# Thermal_imager_Up.net
KiCad netlist of a schematic drawn in Altium Designer
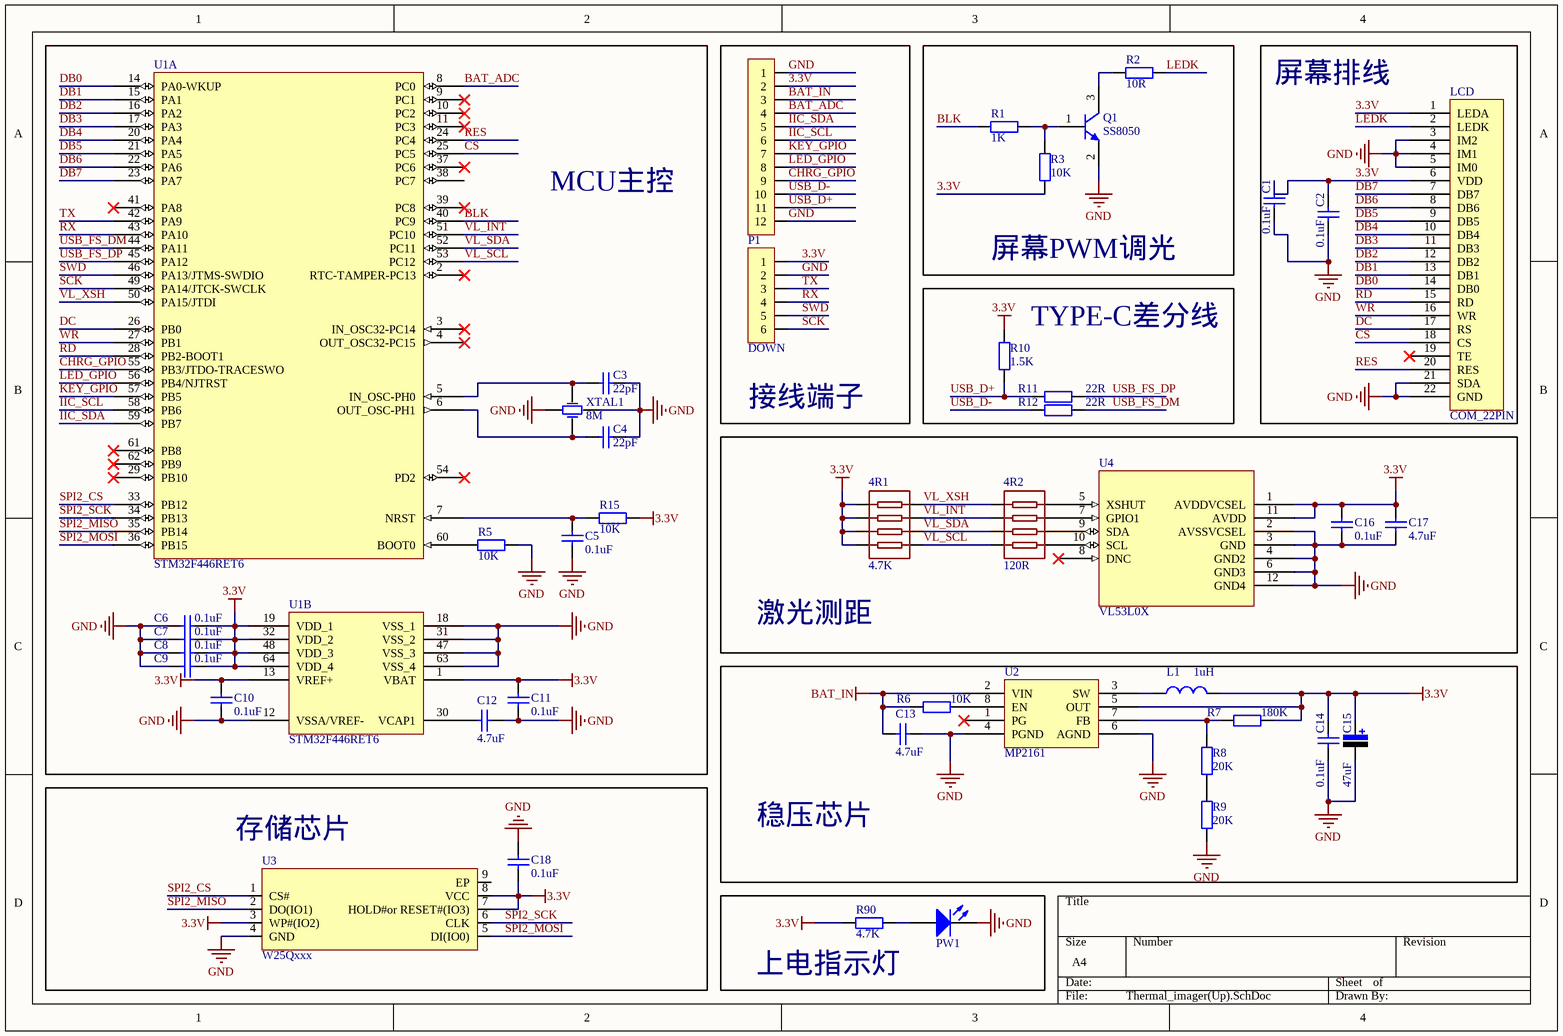
[diagram p0: Thermal_imager(Up).SchDoc]

(export (version "E")
  (design (tool "Eeschema 10.0.6"))
  (components
    (comp (ref "4R1") (value "4.7K") (footprint "R_4R") (libsource (lib "Zfy_Library") (part "4R")))
    (comp (ref "4R2") (value "120R") (footprint "R_4R") (libsource (lib "Zfy_Library") (part "4R")))
    (comp (ref "C1")
      (value "0.1uF")
      (footprint "LC-0603_C")
      (description "无极性电容")
      (fields (field (name "PUBLISHER") "Altium Limited"))
      (libsource (lib "Fszhang") (part "Cap"))
    )
    (comp (ref "C2")
      (value "0.1uF")
      (footprint "LC-0603_C")
      (description "无极性电容")
      (fields (field (name "PUBLISHER") "Altium Limited"))
      (libsource (lib "Fszhang") (part "Cap"))
    )
    (comp (ref "C3")
      (value "22pF")
      (footprint "LC-0603_C")
      (description "无极性电容")
      (fields (field (name "Comment") "Cap") (field (name "PUBLISHER") "Altium Limited"))
      (libsource (lib "Fszhang") (part "Cap"))
    )
    (comp (ref "C4")
      (value "22pF")
      (footprint "LC-0603_C")
      (description "无极性电容")
      (fields (field (name "Comment") "Cap") (field (name "PUBLISHER") "Altium Limited"))
      (libsource (lib "Fszhang") (part "Cap"))
    )
    (comp (ref "C5")
      (value "0.1uF")
      (footprint "LC-0603_C")
      (description "无极性电容")
      (fields (field (name "PUBLISHER") "Altium Limited"))
      (libsource (lib "Fszhang") (part "Cap"))
    )
    (comp (ref "C6")
      (value "0.1uF")
      (footprint "LC-0603_C")
      (description "无极性电容")
      (fields (field (name "PUBLISHER") "Altium Limited"))
      (libsource (lib "Fszhang") (part "Cap"))
    )
    (comp (ref "C7")
      (value "0.1uF")
      (footprint "LC-0603_C")
      (description "无极性电容")
      (fields (field (name "PUBLISHER") "Altium Limited"))
      (libsource (lib "Fszhang") (part "Cap"))
    )
    (comp (ref "C8")
      (value "0.1uF")
      (footprint "LC-0603_C")
      (description "无极性电容")
      (fields (field (name "PUBLISHER") "Altium Limited"))
      (libsource (lib "Fszhang") (part "Cap"))
    )
    (comp (ref "C9")
      (value "0.1uF")
      (footprint "LC-0603_C")
      (description "无极性电容")
      (fields (field (name "PUBLISHER") "Altium Limited"))
      (libsource (lib "Fszhang") (part "Cap"))
    )
    (comp (ref "C10")
      (value "0.1uF")
      (footprint "LC-0603_C")
      (description "无极性电容")
      (fields (field (name "PUBLISHER") "Altium Limited"))
      (libsource (lib "Fszhang") (part "Cap"))
    )
    (comp (ref "C11")
      (value "0.1uF")
      (footprint "LC-0603_C")
      (description "无极性电容")
      (fields (field (name "PUBLISHER") "Altium Limited"))
      (libsource (lib "Fszhang") (part "Cap"))
    )
    (comp (ref "C12")
      (value "4.7uF")
      (footprint "LC-0603_C")
      (description "无极性电容")
      (fields (field (name "PUBLISHER") "Altium Limited"))
      (libsource (lib "Fszhang") (part "Cap"))
    )
    (comp (ref "C13")
      (value "4.7uF")
      (footprint "LC-1206_C")
      (description "无极性电容")
      (fields (field (name "PUBLISHER") "Altium Limited"))
      (libsource (lib "Fszhang") (part "Cap"))
    )
    (comp (ref "C14")
      (value "0.1uF")
      (footprint "LC-0603_C")
      (description "无极性电容")
      (fields (field (name "PUBLISHER") "Altium Limited"))
      (libsource (lib "Fszhang") (part "Cap"))
    )
    (comp (ref "C15")
      (value "47uF")
      (footprint "CAP-3528")
      (description "极性电解电容")
      (fields (field (name "PUBLISHER") "Altium Limited"))
      (libsource (lib "Fszhang") (part "Cap Pol"))
    )
    (comp (ref "C16")
      (value "0.1uF")
      (footprint "LC-0603_C")
      (description "无极性电容")
      (fields (field (name "PUBLISHER") "Altium Limited"))
      (libsource (lib "Fszhang") (part "Cap"))
    )
    (comp (ref "C17")
      (value "4.7uF")
      (footprint "LC-0603_C")
      (description "无极性电容")
      (fields (field (name "PUBLISHER") "Altium Limited"))
      (libsource (lib "Fszhang") (part "Cap"))
    )
    (comp (ref "C18")
      (value "0.1uF")
      (footprint "LC-0603_C")
      (description "无极性电容")
      (fields (field (name "PUBLISHER") "Altium Limited"))
      (libsource (lib "Fszhang") (part "Cap"))
    )
    (comp (ref "DOWN")
      (value "Header 6*1")
      (footprint "COM_W_2.0_6P")
      (description "接插件")
      (fields (field (name "PUBLISHER") "Altium Limited"))
      (libsource (lib "Connect") (part "Header 6*1"))
    )
    (comp (ref "L1")
      (value "1uH")
      (footprint "Inductor-SWPA4030")
      (description "电感")
      (fields (field (name "Comment") "Inductor") (field (name "PUBLISHER") "Altium Limited"))
      (libsource (lib "Fszhang") (part "Inductor"))
    )
    (comp (ref "LCD")
      (value "COM_22PIN")
      (footprint "FPC_22PIN_0.5")
      (libsource (lib "Zfy_Library") (part "COM_22PIN"))
    )
    (comp (ref "P1")
      (value "Header 12*1")
      (footprint "HDR12X1_A-1.27mm")
      (description "接插件")
      (fields (field (name "PUBLISHER") "Altium Limited"))
      (libsource (lib "Connect") (part "Header 12*1"))
    )
    (comp (ref "PW1")
      (value "LED0")
      (footprint "LC-0603_LED_S1")
      (description "发光二极管")
      (fields (field (name "PUBLISHER") "Altium Limited"))
      (libsource (lib "Fszhang") (part "LED0"))
    )
    (comp (ref "Q1")
      (value "SS8050")
      (footprint "SOT-23")
      (description "NPN贴片三极管")
      (fields (field (name "PUBLISHER") "Altium Limited"))
      (libsource (lib "Fszhang") (part "SS8050"))
    )
    (comp (ref "R1")
      (value "1K")
      (footprint "LC-0603_R")
      (description "贴片电阻")
      (fields (field (name "PUBLISHER") "Altium Limited"))
      (libsource (lib "Fszhang") (part "=VALUE"))
    )
    (comp (ref "R2")
      (value "10R")
      (footprint "LC-0603_R")
      (description "贴片电阻")
      (fields (field (name "PUBLISHER") "Altium Limited"))
      (libsource (lib "Fszhang") (part "=VALUE"))
    )
    (comp (ref "R3")
      (value "10K")
      (footprint "LC-0603_R")
      (description "贴片电阻")
      (fields (field (name "PUBLISHER") "Altium Limited"))
      (libsource (lib "") (part "=VALUE_1"))
    )
    (comp (ref "R5")
      (value "10K")
      (footprint "LC-0603_R")
      (description "贴片电阻")
      (fields (field (name "PUBLISHER") "Altium Limited"))
      (libsource (lib "Fszhang") (part "=VALUE"))
    )
    (comp (ref "R6")
      (value "10K")
      (footprint "LC-0603_R")
      (description "贴片电阻")
      (fields (field (name "PUBLISHER") "Altium Limited"))
      (libsource (lib "Fszhang") (part "=VALUE"))
    )
    (comp (ref "R7")
      (value "180K")
      (footprint "LC-0603_R")
      (description "贴片电阻")
      (fields (field (name "PUBLISHER") "Altium Limited"))
      (libsource (lib "Fszhang") (part "=VALUE"))
    )
    (comp (ref "R8")
      (value "20K")
      (footprint "LC-0603_R")
      (description "贴片电阻")
      (fields (field (name "PUBLISHER") "Altium Limited"))
      (libsource (lib "") (part "=VALUE_1"))
    )
    (comp (ref "R9")
      (value "20K")
      (footprint "LC-0603_R")
      (description "贴片电阻")
      (fields (field (name "PUBLISHER") "Altium Limited"))
      (libsource (lib "") (part "=VALUE_1"))
    )
    (comp (ref "R10")
      (value "1.5K")
      (footprint "LC-0603_R")
      (description "贴片电阻")
      (fields (field (name "PUBLISHER") "Altium Limited"))
      (libsource (lib "") (part "=VALUE_1"))
    )
    (comp (ref "R11")
      (value "22R")
      (footprint "LC-0603_R")
      (description "贴片电阻")
      (fields (field (name "PUBLISHER") "Altium Limited"))
      (libsource (lib "Fszhang") (part "=VALUE"))
    )
    (comp (ref "R12")
      (value "22R")
      (footprint "LC-0603_R")
      (description "贴片电阻")
      (fields (field (name "PUBLISHER") "Altium Limited"))
      (libsource (lib "Fszhang") (part "=VALUE"))
    )
    (comp (ref "R15")
      (value "10K")
      (footprint "LC-0603_R")
      (description "贴片电阻")
      (fields (field (name "PUBLISHER") "Altium Limited"))
      (libsource (lib "Fszhang") (part "=VALUE"))
    )
    (comp (ref "R90")
      (value "4.7K")
      (footprint "LC-0603_R")
      (description "贴片电阻")
      (fields (field (name "Comment") "Res1") (field (name "PUBLISHER") "Altium Limited"))
      (libsource (lib "Fszhang") (part "Res1"))
    )
    (comp (ref "U1")
      (value "STM32F446RET6")
      (footprint "LQFP64_L")
      (libsource (lib "Fszhang") (part "Y-STM32F446RET6"))
    )
    (comp (ref "U2")
      (value "MP2161")
      (footprint "SOT-23-8_MP2161")
      (libsource (lib "Zfy_Library") (part "MP2161"))
    )
    (comp (ref "U3")
      (value "W25Qxxx")
      (footprint "WSON-8_W25Qxxx")
      (libsource (lib "Zfy_Library") (part "W25Qxxx"))
    )
    (comp (ref "U4") (value "VL53L0X") (footprint "VL53L0X") (libsource (lib "Zfy_Library") (part "VL53L0X")))
    (comp (ref "XTAL1")
      (value "8M")
      (footprint "XTAL_3225_4Pin")
      (libsource (lib "Zfy_Library") (part "XTAL_5032"))
    )
  )
  (nets
    (net (code "1") (name "/BAT_ADC") (class "Default")
      (node (ref "P1") (pin "4") (pinfunction "4_4") (pintype "passive"))
      (node (ref "U1") (pin "8") (pinfunction "PC0_8") (pintype "bidirectional"))
    )
    (net (code "2") (name "/BLK") (class "Default")
      (node (ref "R1") (pin "2") (pinfunction "2_2") (pintype "passive"))
      (node (ref "U1") (pin "40") (pinfunction "PC9_40") (pintype "bidirectional"))
    )
    (net (code "3") (name "/CHRG_GPIO") (class "Default")
      (node (ref "P1") (pin "9") (pinfunction "9_9") (pintype "passive"))
      (node (ref "U1") (pin "55") (pinfunction "PB3/JTDO-TRACESWO_55") (pintype "bidirectional"))
    )
    (net (code "4") (name "/CS") (class "Default")
      (node (ref "LCD") (pin "18") (pinfunction "CS_18") (pintype "passive"))
      (node (ref "U1") (pin "25") (pinfunction "PC5_25") (pintype "bidirectional"))
    )
    (net (code "5") (name "/DB0") (class "Default")
      (node (ref "LCD") (pin "14") (pinfunction "DB0_14") (pintype "passive"))
      (node (ref "U1") (pin "14") (pinfunction "PA0-WKUP_14") (pintype "bidirectional"))
    )
    (net (code "6") (name "/DB1") (class "Default")
      (node (ref "LCD") (pin "13") (pinfunction "DB1_13") (pintype "passive"))
      (node (ref "U1") (pin "15") (pinfunction "PA1_15") (pintype "bidirectional"))
    )
    (net (code "7") (name "/DB2") (class "Default")
      (node (ref "LCD") (pin "12") (pinfunction "DB2_12") (pintype "passive"))
      (node (ref "U1") (pin "16") (pinfunction "PA2_16") (pintype "bidirectional"))
    )
    (net (code "8") (name "/DB3") (class "Default")
      (node (ref "LCD") (pin "11") (pinfunction "DB3_11") (pintype "passive"))
      (node (ref "U1") (pin "17") (pinfunction "PA3_17") (pintype "bidirectional"))
    )
    (net (code "9") (name "/DB4") (class "Default")
      (node (ref "LCD") (pin "10") (pinfunction "DB4_10") (pintype "passive"))
      (node (ref "U1") (pin "20") (pinfunction "PA4_20") (pintype "bidirectional"))
    )
    (net (code "10") (name "/DB5") (class "Default")
      (node (ref "LCD") (pin "9") (pinfunction "DB5_9") (pintype "passive"))
      (node (ref "U1") (pin "21") (pinfunction "PA5_21") (pintype "bidirectional"))
    )
    (net (code "11") (name "/DB6") (class "Default")
      (node (ref "LCD") (pin "8") (pinfunction "DB6_8") (pintype "passive"))
      (node (ref "U1") (pin "22") (pinfunction "PA6_22") (pintype "bidirectional"))
    )
    (net (code "12") (name "/DB7") (class "Default")
      (node (ref "LCD") (pin "7") (pinfunction "DB7_7") (pintype "passive"))
      (node (ref "U1") (pin "23") (pinfunction "PA7_23") (pintype "bidirectional"))
    )
    (net (code "13") (name "/DC") (class "Default")
      (node (ref "LCD") (pin "17") (pinfunction "RS_17") (pintype "passive"))
      (node (ref "U1") (pin "26") (pinfunction "PB0_26") (pintype "bidirectional"))
    )
    (net (code "14") (name "/IIC_SCL") (class "Default")
      (node (ref "P1") (pin "6") (pinfunction "6_6") (pintype "passive"))
      (node (ref "U1") (pin "58") (pinfunction "PB6_58") (pintype "bidirectional"))
    )
    (net (code "15") (name "/IIC_SDA") (class "Default")
      (node (ref "P1") (pin "5") (pinfunction "5_5") (pintype "passive"))
      (node (ref "U1") (pin "59") (pinfunction "PB7_59") (pintype "bidirectional"))
    )
    (net (code "16") (name "/KEY_GPIO") (class "Default")
      (node (ref "P1") (pin "7") (pinfunction "7_7") (pintype "passive"))
      (node (ref "U1") (pin "57") (pinfunction "PB5_57") (pintype "bidirectional"))
    )
    (net (code "17") (name "/LEDK") (class "Default")
      (node (ref "LCD") (pin "2") (pinfunction "LEDK_2") (pintype "passive"))
      (node (ref "R2") (pin "1") (pinfunction "1_1") (pintype "passive"))
    )
    (net (code "18") (name "/LED_GPIO") (class "Default")
      (node (ref "P1") (pin "8") (pinfunction "8_8") (pintype "passive"))
      (node (ref "U1") (pin "56") (pinfunction "PB4/NJTRST_56") (pintype "bidirectional"))
    )
    (net (code "19") (name "/RD") (class "Default")
      (node (ref "LCD") (pin "15") (pinfunction "RD_15") (pintype "passive"))
      (node (ref "U1") (pin "28") (pinfunction "PB2-BOOT1_28") (pintype "bidirectional"))
    )
    (net (code "20") (name "/RES") (class "Default")
      (node (ref "LCD") (pin "20") (pinfunction "RES_20") (pintype "passive"))
      (node (ref "U1") (pin "24") (pinfunction "PC4_24") (pintype "bidirectional"))
    )
    (net (code "21") (name "/RX") (class "Default")
      (node (ref "DOWN") (pin "4") (pinfunction "4_4") (pintype "passive"))
      (node (ref "U1") (pin "43") (pinfunction "PA10_43") (pintype "bidirectional"))
    )
    (net (code "22") (name "/SCK") (class "Default")
      (node (ref "DOWN") (pin "6") (pinfunction "6_6") (pintype "passive"))
      (node (ref "U1") (pin "49") (pinfunction "PA14/JTCK-SWCLK_49") (pintype "bidirectional"))
    )
    (net (code "23") (name "/SPI2_CS") (class "Default")
      (node (ref "U1") (pin "33") (pinfunction "PB12_33") (pintype "bidirectional"))
      (node (ref "U3") (pin "1") (pinfunction "CS#_1") (pintype "passive"))
    )
    (net (code "24") (name "/SPI2_MISO") (class "Default")
      (node (ref "U1") (pin "35") (pinfunction "PB14_35") (pintype "bidirectional"))
      (node (ref "U3") (pin "2") (pinfunction "DO(IO1)_2") (pintype "passive"))
    )
    (net (code "25") (name "/SPI2_MOSI") (class "Default")
      (node (ref "U1") (pin "36") (pinfunction "PB15_36") (pintype "bidirectional"))
      (node (ref "U3") (pin "5") (pinfunction "DI(IO0)_5") (pintype "passive"))
    )
    (net (code "26") (name "/SPI2_SCK") (class "Default")
      (node (ref "U1") (pin "34") (pinfunction "PB13_34") (pintype "bidirectional"))
      (node (ref "U3") (pin "6") (pinfunction "CLK_6") (pintype "passive"))
    )
    (net (code "27") (name "/SWD") (class "Default")
      (node (ref "DOWN") (pin "5") (pinfunction "5_5") (pintype "passive"))
      (node (ref "U1") (pin "46") (pinfunction "PA13/JTMS-SWDIO_46") (pintype "bidirectional"))
    )
    (net (code "28") (name "/TX") (class "Default")
      (node (ref "DOWN") (pin "3") (pinfunction "3_3") (pintype "passive"))
      (node (ref "U1") (pin "42") (pinfunction "PA9_42") (pintype "bidirectional"))
    )
    (net (code "29") (name "/USB_D+") (class "Default")
      (node (ref "P1") (pin "11") (pinfunction "11_11") (pintype "passive"))
      (node (ref "R10") (pin "2") (pinfunction "2_2") (pintype "passive"))
      (node (ref "R11") (pin "2") (pinfunction "2_2") (pintype "passive"))
    )
    (net (code "30") (name "/USB_D-") (class "Default")
      (node (ref "P1") (pin "10") (pinfunction "10_10") (pintype "passive"))
      (node (ref "R12") (pin "2") (pinfunction "2_2") (pintype "passive"))
    )
    (net (code "31") (name "/USB_FS_DM") (class "Default")
      (node (ref "R12") (pin "1") (pinfunction "1_1") (pintype "passive"))
      (node (ref "U1") (pin "44") (pinfunction "PA11_44") (pintype "bidirectional"))
    )
    (net (code "32") (name "/USB_FS_DP") (class "Default")
      (node (ref "R11") (pin "1") (pinfunction "1_1") (pintype "passive"))
      (node (ref "U1") (pin "45") (pinfunction "PA12_45") (pintype "bidirectional"))
    )
    (net (code "33") (name "/VL_INT") (class "Default")
      (node (ref "4R1") (pin "7") (pinfunction "7_7") (pintype "passive"))
      (node (ref "4R2") (pin "2") (pinfunction "2_2") (pintype "passive"))
      (node (ref "U1") (pin "51") (pinfunction "PC10_51") (pintype "bidirectional"))
    )
    (net (code "34") (name "/VL_SCL") (class "Default")
      (node (ref "4R1") (pin "5") (pinfunction "5_5") (pintype "passive"))
      (node (ref "4R2") (pin "4") (pinfunction "4_4") (pintype "passive"))
      (node (ref "U1") (pin "53") (pinfunction "PC12_53") (pintype "bidirectional"))
    )
    (net (code "35") (name "/VL_SDA") (class "Default")
      (node (ref "4R1") (pin "6") (pinfunction "6_6") (pintype "passive"))
      (node (ref "4R2") (pin "3") (pinfunction "3_3") (pintype "passive"))
      (node (ref "U1") (pin "52") (pinfunction "PC11_52") (pintype "bidirectional"))
    )
    (net (code "36") (name "/VL_XSH") (class "Default")
      (node (ref "4R1") (pin "8") (pinfunction "8_8") (pintype "passive"))
      (node (ref "4R2") (pin "1") (pinfunction "1_1") (pintype "passive"))
      (node (ref "U1") (pin "50") (pinfunction "PA15/JTDI_50") (pintype "bidirectional"))
    )
    (net (code "37") (name "/WR") (class "Default")
      (node (ref "LCD") (pin "16") (pinfunction "WR_16") (pintype "passive"))
      (node (ref "U1") (pin "27") (pinfunction "PB1_27") (pintype "bidirectional"))
    )
    (net (code "38") (name "3.3V") (class "Default")
      (node (ref "4R1") (pin "1") (pinfunction "1_1") (pintype "passive"))
      (node (ref "4R1") (pin "2") (pinfunction "2_2") (pintype "passive"))
      (node (ref "4R1") (pin "3") (pinfunction "3_3") (pintype "passive"))
      (node (ref "4R1") (pin "4") (pinfunction "4_4") (pintype "passive"))
      (node (ref "C1") (pin "2") (pinfunction "2_2") (pintype "passive"))
      (node (ref "C10") (pin "2") (pinfunction "2_2") (pintype "passive"))
      (node (ref "C11") (pin "2") (pinfunction "2_2") (pintype "passive"))
      (node (ref "C14") (pin "2") (pinfunction "2_2") (pintype "passive"))
      (node (ref "C15") (pin "1") (pinfunction "1_1") (pintype "passive"))
      (node (ref "C16") (pin "2") (pinfunction "2_2") (pintype "passive"))
      (node (ref "C17") (pin "2") (pinfunction "2_2") (pintype "passive"))
      (node (ref "C18") (pin "1") (pinfunction "1_1") (pintype "passive"))
      (node (ref "C2") (pin "2") (pinfunction "2_2") (pintype "passive"))
      (node (ref "C6") (pin "2") (pinfunction "2_2") (pintype "passive"))
      (node (ref "C7") (pin "2") (pinfunction "2_2") (pintype "passive"))
      (node (ref "C8") (pin "2") (pinfunction "2_2") (pintype "passive"))
      (node (ref "C9") (pin "2") (pinfunction "2_2") (pintype "passive"))
      (node (ref "DOWN") (pin "1") (pinfunction "1_1") (pintype "passive"))
      (node (ref "L1") (pin "2") (pinfunction "2_2") (pintype "passive"))
      (node (ref "LCD") (pin "1") (pinfunction "LEDA_1") (pintype "passive"))
      (node (ref "LCD") (pin "6") (pinfunction "VDD_6") (pintype "passive"))
      (node (ref "P1") (pin "2") (pinfunction "2_2") (pintype "passive"))
      (node (ref "R10") (pin "1") (pinfunction "1_1") (pintype "passive"))
      (node (ref "R15") (pin "1") (pinfunction "1_1") (pintype "passive"))
      (node (ref "R3") (pin "2") (pinfunction "2_2") (pintype "passive"))
      (node (ref "R7") (pin "1") (pinfunction "1_1") (pintype "passive"))
      (node (ref "R90") (pin "1") (pinfunction "1_1") (pintype "passive"))
      (node (ref "U1") (pin "1") (pinfunction "VBAT_1") (pintype "power_in"))
      (node (ref "U1") (pin "13") (pinfunction "VREF+_13") (pintype "power_in"))
      (node (ref "U1") (pin "19") (pinfunction "VDD_1_19") (pintype "power_in"))
      (node (ref "U1") (pin "32") (pinfunction "VDD_2_32") (pintype "power_in"))
      (node (ref "U1") (pin "48") (pinfunction "VDD_3_48") (pintype "power_in"))
      (node (ref "U1") (pin "64") (pinfunction "VDD_4_64") (pintype "power_in"))
      (node (ref "U2") (pin "5") (pinfunction "OUT_5") (pintype "passive"))
      (node (ref "U3") (pin "3") (pinfunction "WP#(IO2)_3") (pintype "passive"))
      (node (ref "U3") (pin "7") (pinfunction "HOLD#or_RESET#(IO3)_7") (pintype "passive"))
      (node (ref "U3") (pin "8") (pinfunction "VCC_8") (pintype "passive"))
      (node (ref "U4") (pin "1") (pinfunction "AVDDVCSEL_1") (pintype "power_in"))
      (node (ref "U4") (pin "11") (pinfunction "AVDD_11") (pintype "power_in"))
    )
    (net (code "39") (name "BAT_IN") (class "Default")
      (node (ref "C13") (pin "2") (pinfunction "2_2") (pintype "passive"))
      (node (ref "P1") (pin "3") (pinfunction "3_3") (pintype "passive"))
      (node (ref "R6") (pin "2") (pinfunction "2_2") (pintype "passive"))
      (node (ref "U2") (pin "2") (pinfunction "VIN_2") (pintype "passive"))
    )
    (net (code "40") (name "GND") (class "Default")
      (node (ref "C1") (pin "1") (pinfunction "1_1") (pintype "passive"))
      (node (ref "C10") (pin "1") (pinfunction "1_1") (pintype "passive"))
      (node (ref "C11") (pin "1") (pinfunction "1_1") (pintype "passive"))
      (node (ref "C12") (pin "1") (pinfunction "1_1") (pintype "passive"))
      (node (ref "C13") (pin "1") (pinfunction "1_1") (pintype "passive"))
      (node (ref "C14") (pin "1") (pinfunction "1_1") (pintype "passive"))
      (node (ref "C15") (pin "2") (pinfunction "2_2") (pintype "passive"))
      (node (ref "C16") (pin "1") (pinfunction "1_1") (pintype "passive"))
      (node (ref "C17") (pin "1") (pinfunction "1_1") (pintype "passive"))
      (node (ref "C18") (pin "2") (pinfunction "2_2") (pintype "passive"))
      (node (ref "C2") (pin "1") (pinfunction "1_1") (pintype "passive"))
      (node (ref "C3") (pin "2") (pinfunction "2_2") (pintype "passive"))
      (node (ref "C4") (pin "2") (pinfunction "2_2") (pintype "passive"))
      (node (ref "C5") (pin "1") (pinfunction "1_1") (pintype "passive"))
      (node (ref "C6") (pin "1") (pinfunction "1_1") (pintype "passive"))
      (node (ref "C7") (pin "1") (pinfunction "1_1") (pintype "passive"))
      (node (ref "C8") (pin "1") (pinfunction "1_1") (pintype "passive"))
      (node (ref "C9") (pin "1") (pinfunction "1_1") (pintype "passive"))
      (node (ref "DOWN") (pin "2") (pinfunction "2_2") (pintype "passive"))
      (node (ref "LCD") (pin "21") (pinfunction "SDA_21") (pintype "passive"))
      (node (ref "LCD") (pin "22") (pinfunction "GND_22") (pintype "passive"))
      (node (ref "LCD") (pin "3") (pinfunction "IM2_3") (pintype "passive"))
      (node (ref "LCD") (pin "4") (pinfunction "IM1_4") (pintype "passive"))
      (node (ref "LCD") (pin "5") (pinfunction "IM0_5") (pintype "passive"))
      (node (ref "P1") (pin "1") (pinfunction "1_1") (pintype "passive"))
      (node (ref "P1") (pin "12") (pinfunction "12_12") (pintype "passive"))
      (node (ref "PW1") (pin "2") (pinfunction "K_2") (pintype "passive"))
      (node (ref "Q1") (pin "2") (pinfunction "E_2") (pintype "passive"))
      (node (ref "R5") (pin "1") (pinfunction "1_1") (pintype "passive"))
      (node (ref "R9") (pin "2") (pinfunction "2_2") (pintype "passive"))
      (node (ref "U1") (pin "12") (pinfunction "VSSA/VREF-_12") (pintype "power_in"))
      (node (ref "U1") (pin "18") (pinfunction "VSS_1_18") (pintype "power_in"))
      (node (ref "U1") (pin "31") (pinfunction "VSS_2_31") (pintype "power_in"))
      (node (ref "U1") (pin "47") (pinfunction "VSS_3_47") (pintype "power_in"))
      (node (ref "U1") (pin "63") (pinfunction "VSS_4_63") (pintype "power_in"))
      (node (ref "U2") (pin "4") (pinfunction "PGND_4") (pintype "passive"))
      (node (ref "U2") (pin "6") (pinfunction "AGND_6") (pintype "passive"))
      (node (ref "U3") (pin "4") (pinfunction "GND_4") (pintype "passive"))
      (node (ref "U4") (pin "12") (pinfunction "GND4_12") (pintype "power_in"))
      (node (ref "U4") (pin "2") (pinfunction "AVSSVCSEL_2") (pintype "power_in"))
      (node (ref "U4") (pin "3") (pinfunction "GND_3") (pintype "power_in"))
      (node (ref "U4") (pin "4") (pinfunction "GND2_4") (pintype "power_in"))
      (node (ref "U4") (pin "6") (pinfunction "GND3_6") (pintype "power_in"))
      (node (ref "XTAL1") (pin "2") (pinfunction "2_2") (pintype "passive"))
      (node (ref "XTAL1") (pin "4") (pinfunction "4_4") (pintype "passive"))
    )
    (net (code "41") (name "Net-(PW1-A)") (class "Default")
      (node (ref "PW1") (pin "1") (pinfunction "A_1") (pintype "passive"))
      (node (ref "R90") (pin "2") (pinfunction "2_2") (pintype "passive"))
    )
    (net (code "42") (name "Net-(Q1-B)") (class "Default")
      (node (ref "Q1") (pin "1") (pinfunction "B_1") (pintype "passive"))
      (node (ref "R1") (pin "1") (pinfunction "1_1") (pintype "passive"))
      (node (ref "R3") (pin "1") (pinfunction "1_1") (pintype "passive"))
    )
    (net (code "43") (name "Net-(Q1-C)") (class "Default")
      (node (ref "Q1") (pin "3") (pinfunction "C_3") (pintype "passive"))
      (node (ref "R2") (pin "2") (pinfunction "2_2") (pintype "passive"))
    )
    (net (code "44") (name "Net-(R8-Pad2)") (class "Default")
      (node (ref "R8") (pin "2") (pinfunction "2_2") (pintype "passive"))
      (node (ref "R9") (pin "1") (pinfunction "1_1") (pintype "passive"))
    )
    (net (code "45") (name "Net-(U1A-BOOT0)") (class "Default")
      (node (ref "R5") (pin "2") (pinfunction "2_2") (pintype "passive"))
      (node (ref "U1") (pin "60") (pinfunction "BOOT0_60") (pintype "input"))
    )
    (net (code "46") (name "Net-(U1A-IN_OSC-PH0)") (class "Default")
      (node (ref "C3") (pin "1") (pinfunction "1_1") (pintype "passive"))
      (node (ref "U1") (pin "5") (pinfunction "IN_OSC-PH0_5") (pintype "input"))
      (node (ref "XTAL1") (pin "1") (pinfunction "1_1") (pintype "passive"))
    )
    (net (code "47") (name "Net-(U1A-NRST)") (class "Default")
      (node (ref "C5") (pin "2") (pinfunction "2_2") (pintype "passive"))
      (node (ref "R15") (pin "2") (pinfunction "2_2") (pintype "passive"))
      (node (ref "U1") (pin "7") (pinfunction "NRST_7") (pintype "input"))
    )
    (net (code "48") (name "Net-(U1A-OUT_OSC-PH1)") (class "Default")
      (node (ref "C4") (pin "1") (pinfunction "1_1") (pintype "passive"))
      (node (ref "U1") (pin "6") (pinfunction "OUT_OSC-PH1_6") (pintype "output"))
      (node (ref "XTAL1") (pin "3") (pinfunction "3_3") (pintype "passive"))
    )
    (net (code "49") (name "Net-(U1B-VCAP1)") (class "Default")
      (node (ref "C12") (pin "2") (pinfunction "2_2") (pintype "passive"))
      (node (ref "U1") (pin "30") (pinfunction "VCAP1_30") (pintype "power_in"))
    )
    (net (code "50") (name "Net-(U2-EN)") (class "Default")
      (node (ref "R6") (pin "1") (pinfunction "1_1") (pintype "passive"))
      (node (ref "U2") (pin "8") (pinfunction "EN_8") (pintype "passive"))
    )
    (net (code "51") (name "Net-(U2-FB)") (class "Default")
      (node (ref "R7") (pin "2") (pinfunction "2_2") (pintype "passive"))
      (node (ref "R8") (pin "1") (pinfunction "1_1") (pintype "passive"))
      (node (ref "U2") (pin "7") (pinfunction "FB_7") (pintype "passive"))
    )
    (net (code "52") (name "Net-(U2-SW)") (class "Default")
      (node (ref "L1") (pin "1") (pinfunction "1_1") (pintype "passive"))
      (node (ref "U2") (pin "3") (pinfunction "SW_3") (pintype "passive"))
    )
    (net (code "53") (name "Net-(U4-GPIO1)") (class "Default")
      (node (ref "4R2") (pin "7") (pinfunction "7_7") (pintype "passive"))
      (node (ref "U4") (pin "7") (pinfunction "GPIO1_7") (pintype "input"))
    )
    (net (code "54") (name "Net-(U4-SCL)") (class "Default")
      (node (ref "4R2") (pin "5") (pinfunction "5_5") (pintype "passive"))
      (node (ref "U4") (pin "10") (pinfunction "SCL_10") (pintype "bidirectional"))
    )
    (net (code "55") (name "Net-(U4-SDA)") (class "Default")
      (node (ref "4R2") (pin "6") (pinfunction "6_6") (pintype "passive"))
      (node (ref "U4") (pin "9") (pinfunction "SDA_9") (pintype "bidirectional"))
    )
    (net (code "56") (name "Net-(U4-XSHUT)") (class "Default")
      (node (ref "4R2") (pin "8") (pinfunction "8_8") (pintype "passive"))
      (node (ref "U4") (pin "5") (pinfunction "XSHUT_5") (pintype "input"))
    )
    (net (code "57") (name "unconnected-(LCD-TE-Pad19)") (class "Default")
      (node (ref "LCD") (pin "19") (pinfunction "TE_19") (pintype "passive+no_connect"))
    )
    (net (code "58") (name "unconnected-(U1A-IN_OSC32-PC14-Pad3)") (class "Default")
      (node (ref "U1") (pin "3") (pinfunction "IN_OSC32-PC14_3") (pintype "input+no_connect"))
    )
    (net (code "59") (name "unconnected-(U1A-OUT_OSC32-PC15-Pad4)") (class "Default")
      (node (ref "U1") (pin "4") (pinfunction "OUT_OSC32-PC15_4") (pintype "output+no_connect"))
    )
    (net (code "60") (name "unconnected-(U1A-PA8-Pad41)") (class "Default")
      (node (ref "U1") (pin "41") (pinfunction "PA8_41") (pintype "bidirectional+no_connect"))
    )
    (net (code "61") (name "unconnected-(U1A-PB8-Pad61)") (class "Default")
      (node (ref "U1") (pin "61") (pinfunction "PB8_61") (pintype "bidirectional+no_connect"))
    )
    (net (code "62") (name "unconnected-(U1A-PB9-Pad62)") (class "Default")
      (node (ref "U1") (pin "62") (pinfunction "PB9_62") (pintype "bidirectional+no_connect"))
    )
    (net (code "63") (name "unconnected-(U1A-PB10-Pad29)") (class "Default")
      (node (ref "U1") (pin "29") (pinfunction "PB10_29") (pintype "bidirectional+no_connect"))
    )
    (net (code "64") (name "unconnected-(U1A-PC1-Pad9)") (class "Default")
      (node (ref "U1") (pin "9") (pinfunction "PC1_9") (pintype "bidirectional+no_connect"))
    )
    (net (code "65") (name "unconnected-(U1A-PC2-Pad10)") (class "Default")
      (node (ref "U1") (pin "10") (pinfunction "PC2_10") (pintype "bidirectional+no_connect"))
    )
    (net (code "66") (name "unconnected-(U1A-PC3-Pad11)") (class "Default")
      (node (ref "U1") (pin "11") (pinfunction "PC3_11") (pintype "bidirectional+no_connect"))
    )
    (net (code "67") (name "unconnected-(U1A-PC6-Pad37)") (class "Default")
      (node (ref "U1") (pin "37") (pinfunction "PC6_37") (pintype "bidirectional+no_connect"))
    )
    (net (code "68") (name "unconnected-(U1A-PC7-Pad38)") (class "Default")
      (node (ref "U1") (pin "38") (pinfunction "PC7_38") (pintype "bidirectional"))
    )
    (net (code "69") (name "unconnected-(U1A-PC8-Pad39)") (class "Default")
      (node (ref "U1") (pin "39") (pinfunction "PC8_39") (pintype "bidirectional+no_connect"))
    )
    (net (code "70") (name "unconnected-(U1A-PD2-Pad54)") (class "Default")
      (node (ref "U1") (pin "54") (pinfunction "PD2_54") (pintype "bidirectional+no_connect"))
    )
    (net (code "71") (name "unconnected-(U1A-RTC-TAMPER-PC13-Pad2)") (class "Default")
      (node (ref "U1") (pin "2") (pinfunction "RTC-TAMPER-PC13_2") (pintype "bidirectional+no_connect"))
    )
    (net (code "72") (name "unconnected-(U2-PG-Pad1)") (class "Default")
      (node (ref "U2") (pin "1") (pinfunction "PG_1") (pintype "passive+no_connect"))
    )
    (net (code "73") (name "unconnected-(U3-EP-Pad9)") (class "Default")
      (node (ref "U3") (pin "9") (pinfunction "EP_9") (pintype "passive"))
    )
    (net (code "74") (name "unconnected-(U4-DNC-Pad8)") (class "Default")
      (node (ref "U4") (pin "8") (pinfunction "DNC_8") (pintype "input+no_connect"))
    )
  )
)
